# IR.net
KiCad netlist of a schematic drawn in Altium Designer
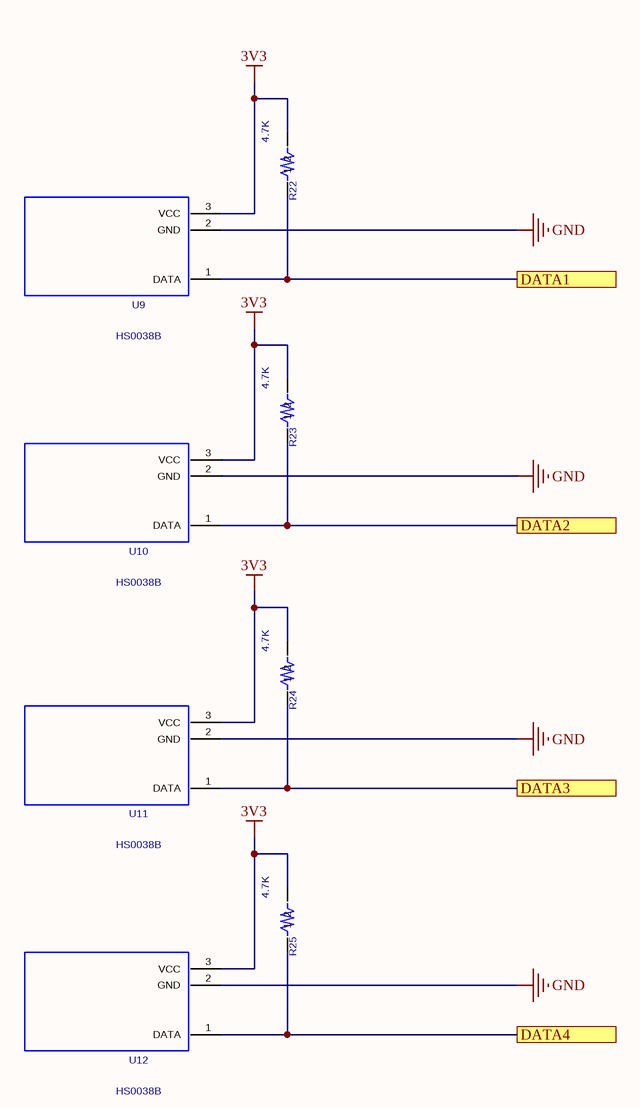
[diagram p0: IR.SchDoc]

(export (version "E")
  (design (tool "Eeschema 10.0.6"))
  (components
    (comp (ref "R22")
      (value "4.7K")
      (footprint "RES_0603_FIRE")
      (description "0402")
      (fields (field (name "TOLERANCE") "+-5%") (field (name "Comment") "RES_4K7_0603_FIRE"))
      (libsource (lib "MINI-V3") (part "RES_4K7_0603_FIRE"))
    )
    (comp (ref "R23")
      (value "4.7K")
      (footprint "RES_0603_FIRE")
      (description "0402")
      (fields (field (name "TOLERANCE") "+-5%") (field (name "Comment") "RES_4K7_0603_FIRE"))
      (libsource (lib "MINI-V3") (part "RES_4K7_0603_FIRE"))
    )
    (comp (ref "R24")
      (value "4.7K")
      (footprint "RES_0603_FIRE")
      (description "0402")
      (fields (field (name "TOLERANCE") "+-5%") (field (name "Comment") "RES_4K7_0603_FIRE"))
      (libsource (lib "MINI-V3") (part "RES_4K7_0603_FIRE"))
    )
    (comp (ref "R25")
      (value "4.7K")
      (footprint "RES_0603_FIRE")
      (description "0402")
      (fields (field (name "TOLERANCE") "+-5%") (field (name "Comment") "RES_4K7_0603_FIRE"))
      (libsource (lib "MINI-V3") (part "RES_4K7_0603_FIRE"))
    )
    (comp (ref "U9") (value "HS0038B") (footprint "HDR1X3") (libsource (lib "MINI-V3") (part "HS0038B")))
    (comp (ref "U10") (value "HS0038B") (footprint "HDR1X3") (libsource (lib "MINI-V3") (part "HS0038B")))
    (comp (ref "U11") (value "HS0038B") (footprint "HDR1X3") (libsource (lib "MINI-V3") (part "HS0038B")))
    (comp (ref "U12") (value "HS0038B") (footprint "HDR1X3") (libsource (lib "MINI-V3") (part "HS0038B")))
  )
  (nets
    (net (code "1") (name "/DATA1") (class "Default")
      (node (ref "R22") (pin "1") (pinfunction "1_1") (pintype "passive"))
      (node (ref "U9") (pin "1") (pinfunction "DATA_1") (pintype "passive"))
    )
    (net (code "2") (name "/DATA2") (class "Default")
      (node (ref "R23") (pin "1") (pinfunction "1_1") (pintype "passive"))
      (node (ref "U10") (pin "1") (pinfunction "DATA_1") (pintype "passive"))
    )
    (net (code "3") (name "/DATA3") (class "Default")
      (node (ref "R24") (pin "1") (pinfunction "1_1") (pintype "passive"))
      (node (ref "U11") (pin "1") (pinfunction "DATA_1") (pintype "passive"))
    )
    (net (code "4") (name "/DATA4") (class "Default")
      (node (ref "R25") (pin "1") (pinfunction "1_1") (pintype "passive"))
      (node (ref "U12") (pin "1") (pinfunction "DATA_1") (pintype "passive"))
    )
    (net (code "5") (name "3V3") (class "Default")
      (node (ref "R22") (pin "2") (pinfunction "2_2") (pintype "passive"))
      (node (ref "R23") (pin "2") (pinfunction "2_2") (pintype "passive"))
      (node (ref "R24") (pin "2") (pinfunction "2_2") (pintype "passive"))
      (node (ref "R25") (pin "2") (pinfunction "2_2") (pintype "passive"))
      (node (ref "U10") (pin "3") (pinfunction "VCC_3") (pintype "passive"))
      (node (ref "U11") (pin "3") (pinfunction "VCC_3") (pintype "passive"))
      (node (ref "U12") (pin "3") (pinfunction "VCC_3") (pintype "passive"))
      (node (ref "U9") (pin "3") (pinfunction "VCC_3") (pintype "passive"))
    )
    (net (code "6") (name "GND") (class "Default")
      (node (ref "U10") (pin "2") (pinfunction "GND_2") (pintype "passive"))
      (node (ref "U11") (pin "2") (pinfunction "GND_2") (pintype "passive"))
      (node (ref "U12") (pin "2") (pinfunction "GND_2") (pintype "passive"))
      (node (ref "U9") (pin "2") (pinfunction "GND_2") (pintype "passive"))
    )
  )
)
